# B2B_Connectors.net
KiCad netlist of a schematic drawn in Altium Designer
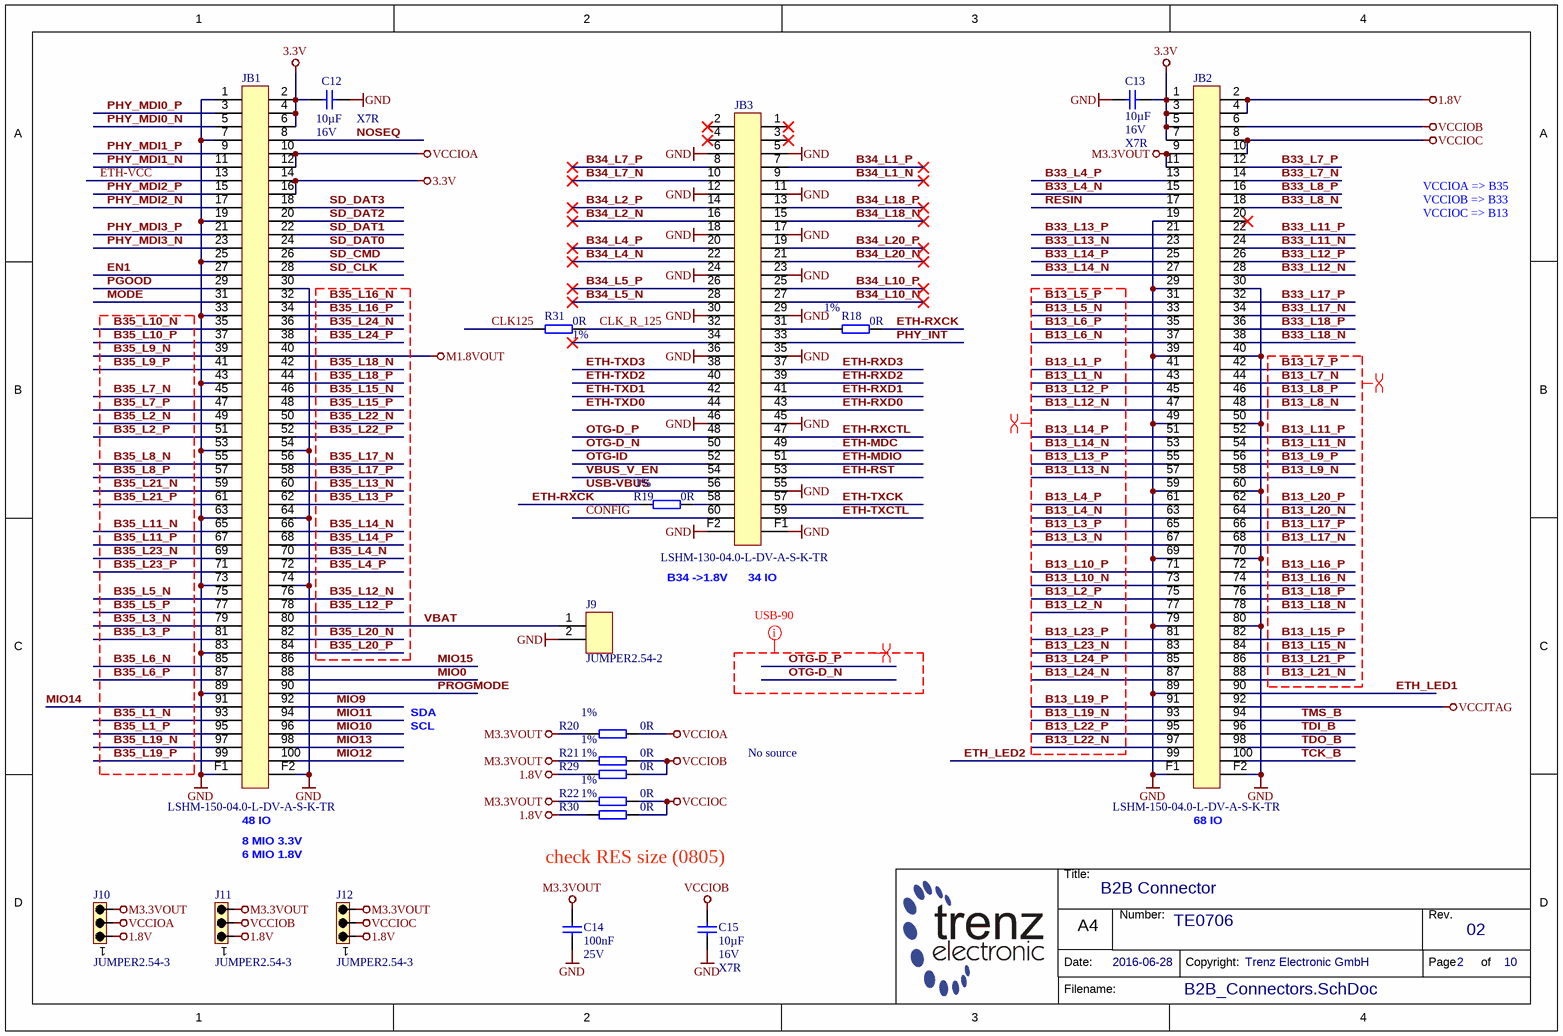
[diagram p0: B2B_Connectors.SchDoc]

(export (version "E")
  (design (tool "Eeschema 10.0.6"))
  (components
    (comp (ref "C12")
      (value "10µF")
      (footprint "CAPC2012X135N")
      (description "KON 10µF 16V X7R SMD 10%")
      (fields
        (field (name "VOLTAGE") "16V")
        (field (name "TECHNOLOGY") "X7R")
        (field (name "TOLERANCE") "10%")
      )
      (libsource (lib "TE") (part "CAP-NP"))
    )
    (comp (ref "C13")
      (value "10µF")
      (footprint "CAPC2012X135N")
      (description "KON 10µF 16V X7R SMD 10%")
      (fields
        (field (name "VOLTAGE") "16V")
        (field (name "TECHNOLOGY") "X7R")
        (field (name "TOLERANCE") "10%")
      )
      (libsource (lib "TE") (part "CAP-NP"))
    )
    (comp (ref "C14")
      (value "100nF")
      (footprint "CAPC1005X55N")
      (description "KON 100nF 25V X5R SMD")
      (fields (field (name "VOLTAGE") "25V"))
      (libsource (lib "TE") (part "CAP-NP"))
    )
    (comp (ref "C15")
      (value "10µF")
      (footprint "CAPC2012X135N")
      (description "KON 10µF 16V X7R SMD 10%")
      (fields
        (field (name "VOLTAGE") "16V")
        (field (name "TECHNOLOGY") "X7R")
        (field (name "TOLERANCE") "10%")
      )
      (libsource (lib "TE") (part "CAP-NP"))
    )
    (comp (ref "J9")
      (value "JUMPER2.54-2")
      (footprint "JUMPER2_54-2")
      (description "Stiftleiste gerade 1-reihig, 2pol.")
      (libsource (lib "TE") (part "CON-2"))
    )
    (comp (ref "J10")
      (value "JUMPER2.54-3")
      (footprint "JUMPER2_54-3")
      (description "Stiftleiste gerade 1-reihig, 3pol.")
      (libsource (lib "TE") (part "JUMPER2.54-3"))
    )
    (comp (ref "J11")
      (value "JUMPER2.54-3")
      (footprint "JUMPER2_54-3")
      (description "Stiftleiste gerade 1-reihig, 3pol.")
      (libsource (lib "TE") (part "JUMPER2.54-3"))
    )
    (comp (ref "J12")
      (value "JUMPER2.54-3")
      (footprint "JUMPER2_54-3")
      (description "Stiftleiste gerade 1-reihig, 3pol.")
      (libsource (lib "TE") (part "JUMPER2.54-3"))
    )
    (comp (ref "JB1")
      (value "LSHM-150-04.0-L-DV-A-S-K-TR")
      (footprint "LSHM-150-XXX-X-DV-A-X")
      (description "Samtec Razor Beam REF⁃189016⁃02, LF-04.0, 100 Pins, für alle 4x5 SoMs")
      (libsource (lib "TE") (part "LSHM-150-XXX-X-XX-A-X"))
    )
    (comp (ref "JB2")
      (value "LSHM-150-04.0-L-DV-A-S-K-TR")
      (footprint "LSHM-150-XXX-X-DV-A-X")
      (description "Samtec Razor Beam REF⁃189016⁃02, LF-04.0, 100 Pins, für alle 4x5 SoMs")
      (libsource (lib "TE") (part "LSHM-150-XXX-X-XX-A-X"))
    )
    (comp (ref "JB3")
      (value "LSHM-130-04.0-L-DV-A-S-K-TR")
      (footprint "LSHM-130-04.0-x-DV-A-S-K-TR")
      (description "Samtec Razor Beam REF⁃189017⁃02, LF-04.0, 60 Pins, für alle 4x5 SoMs")
      (libsource (lib "TE") (part "LSHM-130-XXX-X-XX-A-X"))
    )
    (comp (ref "R18")
      (value "0R")
      (footprint "RESC1005X40N")
      (description "WID SMD 0R")
      (fields (field (name "TOLERANCE") "1%"))
      (libsource (lib "TE") (part "RES"))
    )
    (comp (ref "R19")
      (value "0R")
      (footprint "RESC1005X40N")
      (description "WID SMD 0R")
      (fields (field (name "TOLERANCE") "1%"))
      (libsource (lib "TE") (part "RES"))
    )
    (comp (ref "R20")
      (value "0R")
      (footprint "RESC2012X60N")
      (description "WID SMD 0R 0.125W 2A Brücke")
      (fields (field (name "TOLERANCE") "1%"))
      (libsource (lib "TE") (part "RES"))
    )
    (comp (ref "R21")
      (value "0R")
      (footprint "RESC2012X60N")
      (description "WID SMD 0R 0.125W 2A Brücke")
      (fields (field (name "TOLERANCE") "1%"))
      (libsource (lib "TE") (part "RES"))
    )
    (comp (ref "R22")
      (value "0R")
      (footprint "RESC2012X60N")
      (description "WID SMD 0R 0.125W 2A Brücke")
      (fields (field (name "TOLERANCE") "1%"))
      (libsource (lib "TE") (part "RES"))
    )
    (comp (ref "R29")
      (value "0R")
      (footprint "RESC2012X60N")
      (description "WID SMD 0R 0.125W 2A Brücke")
      (fields (field (name "TOLERANCE") "1%"))
      (libsource (lib "TE") (part "RES"))
    )
    (comp (ref "R30")
      (value "0R")
      (footprint "RESC2012X60N")
      (description "WID SMD 0R 0.125W 2A Brücke")
      (fields (field (name "TOLERANCE") "1%"))
      (libsource (lib "TE") (part "RES"))
    )
    (comp (ref "R31")
      (value "0R")
      (footprint "RESC1005X40N")
      (description "WID SMD 0R")
      (fields (field (name "TOLERANCE") "1%"))
      (libsource (lib "TE") (part "RES"))
    )
  )
  (nets
    (net (code "1") (name "/B13_L1_N") (class "Default")
      (node (ref "JB2") (pin "43") (pinfunction "43_43") (pintype "passive"))
    )
    (net (code "2") (name "/B13_L1_P") (class "Default")
      (node (ref "JB2") (pin "41") (pinfunction "41_41") (pintype "passive"))
    )
    (net (code "3") (name "/B13_L2_N") (class "Default")
      (node (ref "JB2") (pin "77") (pinfunction "77_77") (pintype "passive"))
    )
    (net (code "4") (name "/B13_L2_P") (class "Default")
      (node (ref "JB2") (pin "75") (pinfunction "75_75") (pintype "passive"))
    )
    (net (code "5") (name "/B13_L3_N") (class "Default")
      (node (ref "JB2") (pin "67") (pinfunction "67_67") (pintype "passive"))
    )
    (net (code "6") (name "/B13_L3_P") (class "Default")
      (node (ref "JB2") (pin "65") (pinfunction "65_65") (pintype "passive"))
    )
    (net (code "7") (name "/B13_L4_N") (class "Default")
      (node (ref "JB2") (pin "63") (pinfunction "63_63") (pintype "passive"))
    )
    (net (code "8") (name "/B13_L4_P") (class "Default")
      (node (ref "JB2") (pin "61") (pinfunction "61_61") (pintype "passive"))
    )
    (net (code "9") (name "/B13_L5_N") (class "Default")
      (node (ref "JB2") (pin "33") (pinfunction "33_33") (pintype "passive"))
    )
    (net (code "10") (name "/B13_L5_P") (class "Default")
      (node (ref "JB2") (pin "31") (pinfunction "31_31") (pintype "passive"))
    )
    (net (code "11") (name "/B13_L6_N") (class "Default")
      (node (ref "JB2") (pin "37") (pinfunction "37_37") (pintype "passive"))
    )
    (net (code "12") (name "/B13_L6_P") (class "Default")
      (node (ref "JB2") (pin "35") (pinfunction "35_35") (pintype "passive"))
    )
    (net (code "13") (name "/B13_L7_N") (class "Default")
      (node (ref "JB2") (pin "44") (pinfunction "44_44") (pintype "passive"))
    )
    (net (code "14") (name "/B13_L7_P") (class "Default")
      (node (ref "JB2") (pin "42") (pinfunction "42_42") (pintype "passive"))
    )
    (net (code "15") (name "/B13_L8_N") (class "Default")
      (node (ref "JB2") (pin "48") (pinfunction "48_48") (pintype "passive"))
    )
    (net (code "16") (name "/B13_L8_P") (class "Default")
      (node (ref "JB2") (pin "46") (pinfunction "46_46") (pintype "passive"))
    )
    (net (code "17") (name "/B13_L9_N") (class "Default")
      (node (ref "JB2") (pin "58") (pinfunction "58_58") (pintype "passive"))
    )
    (net (code "18") (name "/B13_L9_P") (class "Default")
      (node (ref "JB2") (pin "56") (pinfunction "56_56") (pintype "passive"))
    )
    (net (code "19") (name "/B13_L10_N") (class "Default")
      (node (ref "JB2") (pin "73") (pinfunction "73_73") (pintype "passive"))
    )
    (net (code "20") (name "/B13_L10_P") (class "Default")
      (node (ref "JB2") (pin "71") (pinfunction "71_71") (pintype "passive"))
    )
    (net (code "21") (name "/B13_L11_N") (class "Default")
      (node (ref "JB2") (pin "54") (pinfunction "54_54") (pintype "passive"))
    )
    (net (code "22") (name "/B13_L11_P") (class "Default")
      (node (ref "JB2") (pin "52") (pinfunction "52_52") (pintype "passive"))
    )
    (net (code "23") (name "/B13_L12_N") (class "Default")
      (node (ref "JB2") (pin "47") (pinfunction "47_47") (pintype "passive"))
    )
    (net (code "24") (name "/B13_L12_P") (class "Default")
      (node (ref "JB2") (pin "45") (pinfunction "45_45") (pintype "passive"))
    )
    (net (code "25") (name "/B13_L13_N") (class "Default")
      (node (ref "JB2") (pin "57") (pinfunction "57_57") (pintype "passive"))
    )
    (net (code "26") (name "/B13_L13_P") (class "Default")
      (node (ref "JB2") (pin "55") (pinfunction "55_55") (pintype "passive"))
    )
    (net (code "27") (name "/B13_L14_N") (class "Default")
      (node (ref "JB2") (pin "53") (pinfunction "53_53") (pintype "passive"))
    )
    (net (code "28") (name "/B13_L14_P") (class "Default")
      (node (ref "JB2") (pin "51") (pinfunction "51_51") (pintype "passive"))
    )
    (net (code "29") (name "/B13_L15_N") (class "Default")
      (node (ref "JB2") (pin "84") (pinfunction "84_84") (pintype "passive"))
    )
    (net (code "30") (name "/B13_L15_P") (class "Default")
      (node (ref "JB2") (pin "82") (pinfunction "82_82") (pintype "passive"))
    )
    (net (code "31") (name "/B13_L16_N") (class "Default")
      (node (ref "JB2") (pin "74") (pinfunction "74_74") (pintype "passive"))
    )
    (net (code "32") (name "/B13_L16_P") (class "Default")
      (node (ref "JB2") (pin "72") (pinfunction "72_72") (pintype "passive"))
    )
    (net (code "33") (name "/B13_L17_N") (class "Default")
      (node (ref "JB2") (pin "68") (pinfunction "68_68") (pintype "passive"))
    )
    (net (code "34") (name "/B13_L17_P") (class "Default")
      (node (ref "JB2") (pin "66") (pinfunction "66_66") (pintype "passive"))
    )
    (net (code "35") (name "/B13_L18_N") (class "Default")
      (node (ref "JB2") (pin "78") (pinfunction "78_78") (pintype "passive"))
    )
    (net (code "36") (name "/B13_L18_P") (class "Default")
      (node (ref "JB2") (pin "76") (pinfunction "76_76") (pintype "passive"))
    )
    (net (code "37") (name "/B13_L19_N") (class "Default")
      (node (ref "JB2") (pin "93") (pinfunction "93_93") (pintype "passive"))
    )
    (net (code "38") (name "/B13_L19_P") (class "Default")
      (node (ref "JB2") (pin "91") (pinfunction "91_91") (pintype "passive"))
    )
    (net (code "39") (name "/B13_L20_N") (class "Default")
      (node (ref "JB2") (pin "64") (pinfunction "64_64") (pintype "passive"))
    )
    (net (code "40") (name "/B13_L20_P") (class "Default")
      (node (ref "JB2") (pin "62") (pinfunction "62_62") (pintype "passive"))
    )
    (net (code "41") (name "/B13_L21_N") (class "Default")
      (node (ref "JB2") (pin "88") (pinfunction "88_88") (pintype "passive"))
    )
    (net (code "42") (name "/B13_L21_P") (class "Default")
      (node (ref "JB2") (pin "86") (pinfunction "86_86") (pintype "passive"))
    )
    (net (code "43") (name "/B13_L22_N") (class "Default")
      (node (ref "JB2") (pin "97") (pinfunction "97_97") (pintype "passive"))
    )
    (net (code "44") (name "/B13_L22_P") (class "Default")
      (node (ref "JB2") (pin "95") (pinfunction "95_95") (pintype "passive"))
    )
    (net (code "45") (name "/B13_L23_N") (class "Default")
      (node (ref "JB2") (pin "83") (pinfunction "83_83") (pintype "passive"))
    )
    (net (code "46") (name "/B13_L23_P") (class "Default")
      (node (ref "JB2") (pin "81") (pinfunction "81_81") (pintype "passive"))
    )
    (net (code "47") (name "/B13_L24_N") (class "Default")
      (node (ref "JB2") (pin "87") (pinfunction "87_87") (pintype "passive"))
    )
    (net (code "48") (name "/B13_L24_P") (class "Default")
      (node (ref "JB2") (pin "85") (pinfunction "85_85") (pintype "passive"))
    )
    (net (code "49") (name "/B33_L4_N") (class "Default")
      (node (ref "JB2") (pin "15") (pinfunction "15_15") (pintype "passive"))
    )
    (net (code "50") (name "/B33_L4_P") (class "Default")
      (node (ref "JB2") (pin "13") (pinfunction "13_13") (pintype "passive"))
    )
    (net (code "51") (name "/B33_L7_N") (class "Default")
      (node (ref "JB2") (pin "14") (pinfunction "14_14") (pintype "passive"))
    )
    (net (code "52") (name "/B33_L7_P") (class "Default")
      (node (ref "JB2") (pin "12") (pinfunction "12_12") (pintype "passive"))
    )
    (net (code "53") (name "/B33_L8_N") (class "Default")
      (node (ref "JB2") (pin "18") (pinfunction "18_18") (pintype "passive"))
    )
    (net (code "54") (name "/B33_L8_P") (class "Default")
      (node (ref "JB2") (pin "16") (pinfunction "16_16") (pintype "passive"))
    )
    (net (code "55") (name "/B33_L11_N") (class "Default")
      (node (ref "JB2") (pin "24") (pinfunction "24_24") (pintype "passive"))
    )
    (net (code "56") (name "/B33_L11_P") (class "Default")
      (node (ref "JB2") (pin "22") (pinfunction "22_22") (pintype "passive"))
    )
    (net (code "57") (name "/B33_L12_N") (class "Default")
      (node (ref "JB2") (pin "28") (pinfunction "28_28") (pintype "passive"))
    )
    (net (code "58") (name "/B33_L12_P") (class "Default")
      (node (ref "JB2") (pin "26") (pinfunction "26_26") (pintype "passive"))
    )
    (net (code "59") (name "/B33_L13_N") (class "Default")
      (node (ref "JB2") (pin "23") (pinfunction "23_23") (pintype "passive"))
    )
    (net (code "60") (name "/B33_L13_P") (class "Default")
      (node (ref "JB2") (pin "21") (pinfunction "21_21") (pintype "passive"))
    )
    (net (code "61") (name "/B33_L14_N") (class "Default")
      (node (ref "JB2") (pin "27") (pinfunction "27_27") (pintype "passive"))
    )
    (net (code "62") (name "/B33_L14_P") (class "Default")
      (node (ref "JB2") (pin "25") (pinfunction "25_25") (pintype "passive"))
    )
    (net (code "63") (name "/B33_L17_N") (class "Default")
      (node (ref "JB2") (pin "34") (pinfunction "34_34") (pintype "passive"))
    )
    (net (code "64") (name "/B33_L17_P") (class "Default")
      (node (ref "JB2") (pin "32") (pinfunction "32_32") (pintype "passive"))
    )
    (net (code "65") (name "/B33_L18_N") (class "Default")
      (node (ref "JB2") (pin "38") (pinfunction "38_38") (pintype "passive"))
    )
    (net (code "66") (name "/B33_L18_P") (class "Default")
      (node (ref "JB2") (pin "36") (pinfunction "36_36") (pintype "passive"))
    )
    (net (code "67") (name "/B34_L1_N") (class "Default")
      (node (ref "JB3") (pin "9") (pinfunction "9_9") (pintype "passive+no_connect"))
    )
    (net (code "68") (name "/B34_L1_P") (class "Default")
      (node (ref "JB3") (pin "7") (pinfunction "7_7") (pintype "passive+no_connect"))
    )
    (net (code "69") (name "/B34_L2_N") (class "Default")
      (node (ref "JB3") (pin "16") (pinfunction "16_16") (pintype "passive+no_connect"))
    )
    (net (code "70") (name "/B34_L2_P") (class "Default")
      (node (ref "JB3") (pin "14") (pinfunction "14_14") (pintype "passive+no_connect"))
    )
    (net (code "71") (name "/B34_L4_N") (class "Default")
      (node (ref "JB3") (pin "22") (pinfunction "22_22") (pintype "passive+no_connect"))
    )
    (net (code "72") (name "/B34_L4_P") (class "Default")
      (node (ref "JB3") (pin "20") (pinfunction "20_20") (pintype "passive+no_connect"))
    )
    (net (code "73") (name "/B34_L5_N") (class "Default")
      (node (ref "JB3") (pin "28") (pinfunction "28_28") (pintype "passive+no_connect"))
    )
    (net (code "74") (name "/B34_L5_P") (class "Default")
      (node (ref "JB3") (pin "26") (pinfunction "26_26") (pintype "passive+no_connect"))
    )
    (net (code "75") (name "/B34_L7_N") (class "Default")
      (node (ref "JB3") (pin "10") (pinfunction "10_10") (pintype "passive+no_connect"))
    )
    (net (code "76") (name "/B34_L7_P") (class "Default")
      (node (ref "JB3") (pin "8") (pinfunction "8_8") (pintype "passive+no_connect"))
    )
    (net (code "77") (name "/B34_L10_N") (class "Default")
      (node (ref "JB3") (pin "27") (pinfunction "27_27") (pintype "passive+no_connect"))
    )
    (net (code "78") (name "/B34_L10_P") (class "Default")
      (node (ref "JB3") (pin "25") (pinfunction "25_25") (pintype "passive+no_connect"))
    )
    (net (code "79") (name "/B34_L18_N") (class "Default")
      (node (ref "JB3") (pin "15") (pinfunction "15_15") (pintype "passive+no_connect"))
    )
    (net (code "80") (name "/B34_L18_P") (class "Default")
      (node (ref "JB3") (pin "13") (pinfunction "13_13") (pintype "passive+no_connect"))
    )
    (net (code "81") (name "/B34_L20_N") (class "Default")
      (node (ref "JB3") (pin "21") (pinfunction "21_21") (pintype "passive+no_connect"))
    )
    (net (code "82") (name "/B34_L20_P") (class "Default")
      (node (ref "JB3") (pin "19") (pinfunction "19_19") (pintype "passive+no_connect"))
    )
    (net (code "83") (name "/B35_L1_N") (class "Default")
      (node (ref "JB1") (pin "93") (pinfunction "93_93") (pintype "passive"))
    )
    (net (code "84") (name "/B35_L1_P") (class "Default")
      (node (ref "JB1") (pin "95") (pinfunction "95_95") (pintype "passive"))
    )
    (net (code "85") (name "/B35_L2_N") (class "Default")
      (node (ref "JB1") (pin "49") (pinfunction "49_49") (pintype "passive"))
    )
    (net (code "86") (name "/B35_L2_P") (class "Default")
      (node (ref "JB1") (pin "51") (pinfunction "51_51") (pintype "passive"))
    )
    (net (code "87") (name "/B35_L3_N") (class "Default")
      (node (ref "JB1") (pin "79") (pinfunction "79_79") (pintype "passive"))
    )
    (net (code "88") (name "/B35_L3_P") (class "Default")
      (node (ref "JB1") (pin "81") (pinfunction "81_81") (pintype "passive"))
    )
    (net (code "89") (name "/B35_L4_N") (class "Default")
      (node (ref "JB1") (pin "70") (pinfunction "70_70") (pintype "passive"))
    )
    (net (code "90") (name "/B35_L4_P") (class "Default")
      (node (ref "JB1") (pin "72") (pinfunction "72_72") (pintype "passive"))
    )
    (net (code "91") (name "/B35_L5_N") (class "Default")
      (node (ref "JB1") (pin "75") (pinfunction "75_75") (pintype "passive"))
    )
    (net (code "92") (name "/B35_L5_P") (class "Default")
      (node (ref "JB1") (pin "77") (pinfunction "77_77") (pintype "passive"))
    )
    (net (code "93") (name "/B35_L6_N") (class "Default")
      (node (ref "JB1") (pin "85") (pinfunction "85_85") (pintype "passive"))
    )
    (net (code "94") (name "/B35_L6_P") (class "Default")
      (node (ref "JB1") (pin "87") (pinfunction "87_87") (pintype "passive"))
    )
    (net (code "95") (name "/B35_L7_N") (class "Default")
      (node (ref "JB1") (pin "45") (pinfunction "45_45") (pintype "passive"))
    )
    (net (code "96") (name "/B35_L7_P") (class "Default")
      (node (ref "JB1") (pin "47") (pinfunction "47_47") (pintype "passive"))
    )
    (net (code "97") (name "/B35_L8_N") (class "Default")
      (node (ref "JB1") (pin "55") (pinfunction "55_55") (pintype "passive"))
    )
    (net (code "98") (name "/B35_L8_P") (class "Default")
      (node (ref "JB1") (pin "57") (pinfunction "57_57") (pintype "passive"))
    )
    (net (code "99") (name "/B35_L9_N") (class "Default")
      (node (ref "JB1") (pin "39") (pinfunction "39_39") (pintype "passive"))
    )
    (net (code "100") (name "/B35_L9_P") (class "Default")
      (node (ref "JB1") (pin "41") (pinfunction "41_41") (pintype "passive"))
    )
    (net (code "101") (name "/B35_L10_N") (class "Default")
      (node (ref "JB1") (pin "35") (pinfunction "35_35") (pintype "passive"))
    )
    (net (code "102") (name "/B35_L10_P") (class "Default")
      (node (ref "JB1") (pin "37") (pinfunction "37_37") (pintype "passive"))
    )
    (net (code "103") (name "/B35_L11_N") (class "Default")
      (node (ref "JB1") (pin "65") (pinfunction "65_65") (pintype "passive"))
    )
    (net (code "104") (name "/B35_L11_P") (class "Default")
      (node (ref "JB1") (pin "67") (pinfunction "67_67") (pintype "passive"))
    )
    (net (code "105") (name "/B35_L12_N") (class "Default")
      (node (ref "JB1") (pin "76") (pinfunction "76_76") (pintype "passive"))
    )
    (net (code "106") (name "/B35_L12_P") (class "Default")
      (node (ref "JB1") (pin "78") (pinfunction "78_78") (pintype "passive"))
    )
    (net (code "107") (name "/B35_L13_N") (class "Default")
      (node (ref "JB1") (pin "60") (pinfunction "60_60") (pintype "passive"))
    )
    (net (code "108") (name "/B35_L13_P") (class "Default")
      (node (ref "JB1") (pin "62") (pinfunction "62_62") (pintype "passive"))
    )
    (net (code "109") (name "/B35_L14_N") (class "Default")
      (node (ref "JB1") (pin "66") (pinfunction "66_66") (pintype "passive"))
    )
    (net (code "110") (name "/B35_L14_P") (class "Default")
      (node (ref "JB1") (pin "68") (pinfunction "68_68") (pintype "passive"))
    )
    (net (code "111") (name "/B35_L15_N") (class "Default")
      (node (ref "JB1") (pin "46") (pinfunction "46_46") (pintype "passive"))
    )
    (net (code "112") (name "/B35_L15_P") (class "Default")
      (node (ref "JB1") (pin "48") (pinfunction "48_48") (pintype "passive"))
    )
    (net (code "113") (name "/B35_L16_N") (class "Default")
      (node (ref "JB1") (pin "32") (pinfunction "32_32") (pintype "passive"))
    )
    (net (code "114") (name "/B35_L16_P") (class "Default")
      (node (ref "JB1") (pin "34") (pinfunction "34_34") (pintype "passive"))
    )
    (net (code "115") (name "/B35_L17_N") (class "Default")
      (node (ref "JB1") (pin "56") (pinfunction "56_56") (pintype "passive"))
    )
    (net (code "116") (name "/B35_L17_P") (class "Default")
      (node (ref "JB1") (pin "58") (pinfunction "58_58") (pintype "passive"))
    )
    (net (code "117") (name "/B35_L18_N") (class "Default")
      (node (ref "JB1") (pin "42") (pinfunction "42_42") (pintype "passive"))
    )
    (net (code "118") (name "/B35_L18_P") (class "Default")
      (node (ref "JB1") (pin "44") (pinfunction "44_44") (pintype "passive"))
    )
    (net (code "119") (name "/B35_L19_N") (class "Default")
      (node (ref "JB1") (pin "97") (pinfunction "97_97") (pintype "passive"))
    )
    (net (code "120") (name "/B35_L19_P") (class "Default")
      (node (ref "JB1") (pin "99") (pinfunction "99_99") (pintype "passive"))
    )
    (net (code "121") (name "/B35_L20_N") (class "Default")
      (node (ref "JB1") (pin "82") (pinfunction "82_82") (pintype "passive"))
    )
    (net (code "122") (name "/B35_L20_P") (class "Default")
      (node (ref "JB1") (pin "84") (pinfunction "84_84") (pintype "passive"))
    )
    (net (code "123") (name "/B35_L21_N") (class "Default")
      (node (ref "JB1") (pin "59") (pinfunction "59_59") (pintype "passive"))
    )
    (net (code "124") (name "/B35_L21_P") (class "Default")
      (node (ref "JB1") (pin "61") (pinfunction "61_61") (pintype "passive"))
    )
    (net (code "125") (name "/B35_L22_N") (class "Default")
      (node (ref "JB1") (pin "50") (pinfunction "50_50") (pintype "passive"))
    )
    (net (code "126") (name "/B35_L22_P") (class "Default")
      (node (ref "JB1") (pin "52") (pinfunction "52_52") (pintype "passive"))
    )
    (net (code "127") (name "/B35_L23_N") (class "Default")
      (node (ref "JB1") (pin "69") (pinfunction "69_69") (pintype "passive"))
    )
    (net (code "128") (name "/B35_L23_P") (class "Default")
      (node (ref "JB1") (pin "71") (pinfunction "71_71") (pintype "passive"))
    )
    (net (code "129") (name "/B35_L24_N") (class "Default")
      (node (ref "JB1") (pin "36") (pinfunction "36_36") (pintype "passive"))
    )
    (net (code "130") (name "/B35_L24_P") (class "Default")
      (node (ref "JB1") (pin "38") (pinfunction "38_38") (pintype "passive"))
    )
    (net (code "131") (name "/CLK125") (class "Default")
      (node (ref "R31") (pin "1") (pinfunction "1_1") (pintype "passive"))
    )
    (net (code "132") (name "/CLK_R_125") (class "Default")
      (node (ref "JB3") (pin "32") (pinfunction "32_32") (pintype "passive"))
      (node (ref "R31") (pin "2") (pinfunction "2_2") (pintype "passive"))
    )
    (net (code "133") (name "/CONFIG") (class "Default")
      (node (ref "JB3") (pin "60") (pinfunction "60_60") (pintype "passive"))
    )
    (net (code "134") (name "/EN1") (class "Default")
      (node (ref "JB1") (pin "27") (pinfunction "27_27") (pintype "passive"))
    )
    (net (code "135") (name "/ETH-MDC") (class "Default")
      (node (ref "JB3") (pin "49") (pinfunction "49_49") (pintype "passive"))
    )
    (net (code "136") (name "/ETH-MDIO") (class "Default")
      (node (ref "JB3") (pin "51") (pinfunction "51_51") (pintype "passive"))
    )
    (net (code "137") (name "/ETH-RST") (class "Default")
      (node (ref "JB3") (pin "53") (pinfunction "53_53") (pintype "passive"))
    )
    (net (code "138") (name "/ETH-RXCK") (class "Default")
      (node (ref "R18") (pin "2") (pinfunction "2_2") (pintype "passive"))
      (node (ref "R19") (pin "1") (pinfunction "1_1") (pintype "passive"))
    )
    (net (code "139") (name "/ETH-RXCTL") (class "Default")
      (node (ref "JB3") (pin "47") (pinfunction "47_47") (pintype "passive"))
    )
    (net (code "140") (name "/ETH-RXD0") (class "Default")
      (node (ref "JB3") (pin "43") (pinfunction "43_43") (pintype "passive"))
    )
    (net (code "141") (name "/ETH-RXD1") (class "Default")
      (node (ref "JB3") (pin "41") (pinfunction "41_41") (pintype "passive"))
    )
    (net (code "142") (name "/ETH-RXD2") (class "Default")
      (node (ref "JB3") (pin "39") (pinfunction "39_39") (pintype "passive"))
    )
    (net (code "143") (name "/ETH-RXD3") (class "Default")
      (node (ref "JB3") (pin "37") (pinfunction "37_37") (pintype "passive"))
    )
    (net (code "144") (name "/ETH-TXCK") (class "Default")
      (node (ref "JB3") (pin "57") (pinfunction "57_57") (pintype "passive"))
    )
    (net (code "145") (name "/ETH-TXCTL") (class "Default")
      (node (ref "JB3") (pin "59") (pinfunction "59_59") (pintype "passive"))
    )
    (net (code "146") (name "/ETH-TXD0") (class "Default")
      (node (ref "JB3") (pin "44") (pinfunction "44_44") (pintype "passive"))
    )
    (net (code "147") (name "/ETH-TXD1") (class "Default")
      (node (ref "JB3") (pin "42") (pinfunction "42_42") (pintype "passive"))
    )
    (net (code "148") (name "/ETH-TXD2") (class "Default")
      (node (ref "JB3") (pin "40") (pinfunction "40_40") (pintype "passive"))
    )
    (net (code "149") (name "/ETH-TXD3") (class "Default")
      (node (ref "JB3") (pin "38") (pinfunction "38_38") (pintype "passive"))
    )
    (net (code "150") (name "/ETH-VCC") (class "Default")
      (node (ref "JB1") (pin "13") (pinfunction "13_13") (pintype "passive"))
    )
    (net (code "151") (name "/ETH_LED1") (class "Default")
      (node (ref "JB2") (pin "90") (pinfunction "90_90") (pintype "passive"))
    )
    (net (code "152") (name "/ETH_LED2") (class "Default")
      (node (ref "JB2") (pin "99") (pinfunction "99_99") (pintype "passive"))
    )
    (net (code "153") (name "/MIO0") (class "Default")
      (node (ref "JB1") (pin "88") (pinfunction "88_88") (pintype "passive"))
    )
    (net (code "154") (name "/MIO9") (class "Default")
      (node (ref "JB1") (pin "92") (pinfunction "92_92") (pintype "passive"))
    )
    (net (code "155") (name "/MIO10") (class "Default")
      (node (ref "JB1") (pin "96") (pinfunction "96_96") (pintype "passive"))
    )
    (net (code "156") (name "/MIO11") (class "Default")
      (node (ref "JB1") (pin "94") (pinfunction "94_94") (pintype "passive"))
    )
    (net (code "157") (name "/MIO12") (class "Default")
      (node (ref "JB1") (pin "100") (pinfunction "100_100") (pintype "passive"))
    )
    (net (code "158") (name "/MIO13") (class "Default")
      (node (ref "JB1") (pin "98") (pinfunction "98_98") (pintype "passive"))
    )
    (net (code "159") (name "/MIO14") (class "Default")
      (node (ref "JB1") (pin "91") (pinfunction "91_91") (pintype "passive"))
    )
    (net (code "160") (name "/MIO15") (class "Default")
      (node (ref "JB1") (pin "86") (pinfunction "86_86") (pintype "passive"))
    )
    (net (code "161") (name "/MODE") (class "Default")
      (node (ref "JB1") (pin "31") (pinfunction "31_31") (pintype "passive"))
    )
    (net (code "162") (name "/NOSEQ") (class "Default")
      (node (ref "JB1") (pin "8") (pinfunction "8_8") (pintype "passive"))
    )
    (net (code "163") (name "/OTG-D_N") (class "Default")
      (node (ref "JB3") (pin "50") (pinfunction "50_50") (pintype "passive"))
    )
    (net (code "164") (name "/OTG-D_P") (class "Default")
      (node (ref "JB3") (pin "48") (pinfunction "48_48") (pintype "passive"))
    )
    (net (code "165") (name "/OTG-ID") (class "Default")
      (node (ref "JB3") (pin "52") (pinfunction "52_52") (pintype "passive"))
    )
    (net (code "166") (name "/PGOOD") (class "Default")
      (node (ref "JB1") (pin "29") (pinfunction "29_29") (pintype "passive"))
    )
    (net (code "167") (name "/PHY_INT") (class "Default")
      (node (ref "JB3") (pin "33") (pinfunction "33_33") (pintype "passive"))
    )
    (net (code "168") (name "/PHY_MDI0_N") (class "Default")
      (node (ref "JB1") (pin "5") (pinfunction "5_5") (pintype "passive"))
    )
    (net (code "169") (name "/PHY_MDI0_P") (class "Default")
      (node (ref "JB1") (pin "3") (pinfunction "3_3") (pintype "passive"))
    )
    (net (code "170") (name "/PHY_MDI1_N") (class "Default")
      (node (ref "JB1") (pin "11") (pinfunction "11_11") (pintype "passive"))
    )
    (net (code "171") (name "/PHY_MDI1_P") (class "Default")
      (node (ref "JB1") (pin "9") (pinfunction "9_9") (pintype "passive"))
    )
    (net (code "172") (name "/PHY_MDI2_N") (class "Default")
      (node (ref "JB1") (pin "17") (pinfunction "17_17") (pintype "passive"))
    )
    (net (code "173") (name "/PHY_MDI2_P") (class "Default")
      (node (ref "JB1") (pin "15") (pinfunction "15_15") (pintype "passive"))
    )
    (net (code "174") (name "/PHY_MDI3_N") (class "Default")
      (node (ref "JB1") (pin "23") (pinfunction "23_23") (pintype "passive"))
    )
    (net (code "175") (name "/PHY_MDI3_P") (class "Default")
      (node (ref "JB1") (pin "21") (pinfunction "21_21") (pintype "passive"))
    )
    (net (code "176") (name "/PROGMODE") (class "Default")
      (node (ref "JB1") (pin "90") (pinfunction "90_90") (pintype "passive"))
    )
    (net (code "177") (name "/RESIN") (class "Default")
      (node (ref "JB2") (pin "17") (pinfunction "17_17") (pintype "passive"))
    )
    (net (code "178") (name "/SD_CLK") (class "Default")
      (node (ref "JB1") (pin "28") (pinfunction "28_28") (pintype "passive"))
    )
    (net (code "179") (name "/SD_CMD") (class "Default")
      (node (ref "JB1") (pin "26") (pinfunction "26_26") (pintype "passive"))
    )
    (net (code "180") (name "/SD_DAT0") (class "Default")
      (node (ref "JB1") (pin "24") (pinfunction "24_24") (pintype "passive"))
    )
    (net (code "181") (name "/SD_DAT1") (class "Default")
      (node (ref "JB1") (pin "22") (pinfunction "22_22") (pintype "passive"))
    )
    (net (code "182") (name "/SD_DAT2") (class "Default")
      (node (ref "JB1") (pin "20") (pinfunction "20_20") (pintype "passive"))
    )
    (net (code "183") (name "/SD_DAT3") (class "Default")
      (node (ref "JB1") (pin "18") (pinfunction "18_18") (pintype "passive"))
    )
    (net (code "184") (name "/TCK_B") (class "Default")
      (node (ref "JB2") (pin "100") (pinfunction "100_100") (pintype "passive"))
    )
    (net (code "185") (name "/TDI_B") (class "Default")
      (node (ref "JB2") (pin "96") (pinfunction "96_96") (pintype "passive"))
    )
    (net (code "186") (name "/TDO_B") (class "Default")
      (node (ref "JB2") (pin "98") (pinfunction "98_98") (pintype "passive"))
    )
    (net (code "187") (name "/TMS_B") (class "Default")
      (node (ref "JB2") (pin "94") (pinfunction "94_94") (pintype "passive"))
    )
    (net (code "188") (name "/USB-VBUS") (class "Default")
      (node (ref "JB3") (pin "56") (pinfunction "56_56") (pintype "passive"))
    )
    (net (code "189") (name "/VBAT") (class "Default")
      (node (ref "J9") (pin "1") (pinfunction "1_1") (pintype "passive"))
      (node (ref "JB1") (pin "80") (pinfunction "80_80") (pintype "passive"))
    )
    (net (code "190") (name "/VBUS_V_EN") (class "Default")
      (node (ref "JB3") (pin "54") (pinfunction "54_54") (pintype "passive"))
    )
    (net (code "191") (name "1.8V") (class "Default")
      (node (ref "J10") (pin "1") (pinfunction "1_1") (pintype "passive"))
      (node (ref "J11") (pin "1") (pinfunction "1_1") (pintype "passive"))
      (node (ref "J12") (pin "1") (pinfunction "1_1") (pintype "passive"))
      (node (ref "JB2") (pin "2") (pinfunction "2_2") (pintype "passive"))
      (node (ref "JB2") (pin "4") (pinfunction "4_4") (pintype "passive"))
      (node (ref "R29") (pin "1") (pinfunction "1_1") (pintype "passive"))
      (node (ref "R30") (pin "1") (pinfunction "1_1") (pintype "passive"))
    )
    (net (code "192") (name "3.3V") (class "Default")
      (node (ref "C12") (pin "2") (pinfunction "2_2") (pintype "passive"))
      (node (ref "C13") (pin "2") (pinfunction "2_2") (pintype "passive"))
      (node (ref "JB1") (pin "14") (pinfunction "14_14") (pintype "passive"))
      (node (ref "JB1") (pin "16") (pinfunction "16_16") (pintype "passive"))
      (node (ref "JB1") (pin "2") (pinfunction "2_2") (pintype "passive"))
      (node (ref "JB1") (pin "4") (pinfunction "4_4") (pintype "passive"))
      (node (ref "JB1") (pin "6") (pinfunction "6_6") (pintype "passive"))
      (node (ref "JB2") (pin "1") (pinfunction "1_1") (pintype "passive"))
      (node (ref "JB2") (pin "3") (pinfunction "3_3") (pintype "passive"))
      (node (ref "JB2") (pin "5") (pinfunction "5_5") (pintype "passive"))
      (node (ref "JB2") (pin "7") (pinfunction "7_7") (pintype "passive"))
    )
    (net (code "193") (name "GND") (class "Default")
      (node (ref "C12") (pin "1") (pinfunction "1_1") (pintype "passive"))
      (node (ref "C13") (pin "1") (pinfunction "1_1") (pintype "passive"))
      (node (ref "C14") (pin "2") (pinfunction "2_2") (pintype "passive"))
      (node (ref "C15") (pin "1") (pinfunction "1_1") (pintype "passive"))
      (node (ref "J9") (pin "2") (pinfunction "2_2") (pintype "passive"))
      (node (ref "JB1") (pin "1") (pinfunction "1_1") (pintype "passive"))
      (node (ref "JB1") (pin "19") (pinfunction "19_19") (pintype "passive"))
      (node (ref "JB1") (pin "25") (pinfunction "25_25") (pintype "passive"))
      (node (ref "JB1") (pin "30") (pinfunction "30_30") (pintype "passive"))
      (node (ref "JB1") (pin "33") (pinfunction "33_33") (pintype "passive"))
      (node (ref "JB1") (pin "43") (pinfunction "43_43") (pintype "passive"))
      (node (ref "JB1") (pin "53") (pinfunction "53_53") (pintype "passive"))
      (node (ref "JB1") (pin "54") (pinfunction "54_54") (pintype "passive"))
      (node (ref "JB1") (pin "63") (pinfunction "63_63") (pintype "passive"))
      (node (ref "JB1") (pin "64") (pinfunction "64_64") (pintype "passive"))
      (node (ref "JB1") (pin "7") (pinfunction "7_7") (pintype "passive"))
      (node (ref "JB1") (pin "73") (pinfunction "73_73") (pintype "passive"))
      (node (ref "JB1") (pin "74") (pinfunction "74_74") (pintype "passive"))
      (node (ref "JB1") (pin "83") (pinfunction "83_83") (pintype "passive"))
      (node (ref "JB1") (pin "89") (pinfunction "89_89") (pintype "passive"))
      (node (ref "JB1") (pin "F1") (pinfunction "Shield_F1") (pintype "passive"))
      (node (ref "JB1") (pin "F2") (pinfunction "Shield_F2") (pintype "passive"))
      (node (ref "JB2") (pin "19") (pinfunction "19_19") (pintype "passive"))
      (node (ref "JB2") (pin "29") (pinfunction "29_29") (pintype "passive"))
      (node (ref "JB2") (pin "30") (pinfunction "30_30") (pintype "passive"))
      (node (ref "JB2") (pin "39") (pinfunction "39_39") (pintype "passive"))
      (node (ref "JB2") (pin "40") (pinfunction "40_40") (pintype "passive"))
      (node (ref "JB2") (pin "49") (pinfunction "49_49") (pintype "passive"))
      (node (ref "JB2") (pin "50") (pinfunction "50_50") (pintype "passive"))
      (node (ref "JB2") (pin "59") (pinfunction "59_59") (pintype "passive"))
      (node (ref "JB2") (pin "60") (pinfunction "60_60") (pintype "passive"))
      (node (ref "JB2") (pin "69") (pinfunction "69_69") (pintype "passive"))
      (node (ref "JB2") (pin "70") (pinfunction "70_70") (pintype "passive"))
      (node (ref "JB2") (pin "79") (pinfunction "79_79") (pintype "passive"))
      (node (ref "JB2") (pin "80") (pinfunction "80_80") (pintype "passive"))
      (node (ref "JB2") (pin "89") (pinfunction "89_89") (pintype "passive"))
      (node (ref "JB2") (pin "F1") (pinfunction "Shield_F1") (pintype "passive"))
      (node (ref "JB2") (pin "F2") (pinfunction "Shield_F2") (pintype "passive"))
      (node (ref "JB3") (pin "11") (pinfunction "11_11") (pintype "passive"))
      (node (ref "JB3") (pin "12") (pinfunction "12_12") (pintype "passive"))
      (node (ref "JB3") (pin "17") (pinfunction "17_17") (pintype "passive"))
      (node (ref "JB3") (pin "18") (pinfunction "18_18") (pintype "passive"))
      (node (ref "JB3") (pin "23") (pinfunction "23_23") (pintype "passive"))
      (node (ref "JB3") (pin "24") (pinfunction "24_24") (pintype "passive"))
      (node (ref "JB3") (pin "29") (pinfunction "29_29") (pintype "passive"))
      (node (ref "JB3") (pin "30") (pinfunction "30_30") (pintype "passive"))
      (node (ref "JB3") (pin "35") (pinfunction "35_35") (pintype "passive"))
      (node (ref "JB3") (pin "36") (pinfunction "36_36") (pintype "passive"))
      (node (ref "JB3") (pin "45") (pinfunction "45_45") (pintype "passive"))
      (node (ref "JB3") (pin "46") (pinfunction "46_46") (pintype "passive"))
      (node (ref "JB3") (pin "5") (pinfunction "5_5") (pintype "passive"))
      (node (ref "JB3") (pin "55") (pinfunction "55_55") (pintype "passive"))
      (node (ref "JB3") (pin "6") (pinfunction "6_6") (pintype "passive"))
      (node (ref "JB3") (pin "F1") (pinfunction "Shield_F1") (pintype "passive"))
      (node (ref "JB3") (pin "F2") (pinfunction "Shield_F2") (pintype "passive"))
    )
    (net (code "194") (name "M1.8VOUT") (class "Default")
      (node (ref "JB1") (pin "40") (pinfunction "40_40") (pintype "passive"))
    )
    (net (code "195") (name "M3.3VOUT") (class "Default")
      (node (ref "C14") (pin "1") (pinfunction "1_1") (pintype "passive"))
      (node (ref "J10") (pin "3") (pinfunction "3_3") (pintype "passive"))
      (node (ref "J11") (pin "3") (pinfunction "3_3") (pintype "passive"))
      (node (ref "J12") (pin "3") (pinfunction "3_3") (pintype "passive"))
      (node (ref "JB2") (pin "11") (pinfunction "11_11") (pintype "passive"))
      (node (ref "JB2") (pin "9") (pinfunction "9_9") (pintype "passive"))
      (node (ref "R20") (pin "1") (pinfunction "1_1") (pintype "passive"))
      (node (ref "R21") (pin "1") (pinfunction "1_1") (pintype "passive"))
      (node (ref "R22") (pin "1") (pinfunction "1_1") (pintype "passive"))
    )
    (net (code "196") (name "Net-(JB3-Pad31)") (class "Default")
      (node (ref "JB3") (pin "31") (pinfunction "31_31") (pintype "passive"))
      (node (ref "R18") (pin "1") (pinfunction "1_1") (pintype "passive"))
    )
    (net (code "197") (name "Net-(JB3-Pad58)") (class "Default")
      (node (ref "JB3") (pin "58") (pinfunction "58_58") (pintype "passive"))
      (node (ref "R19") (pin "2") (pinfunction "2_2") (pintype "passive"))
    )
    (net (code "198") (name "VCCIOA") (class "Default")
      (node (ref "J10") (pin "2") (pinfunction "2_2") (pintype "passive"))
      (node (ref "JB1") (pin "10") (pinfunction "10_10") (pintype "passive"))
      (node (ref "JB1") (pin "12") (pinfunction "12_12") (pintype "passive"))
      (node (ref "R20") (pin "2") (pinfunction "2_2") (pintype "passive"))
    )
    (net (code "199") (name "VCCIOB") (class "Default")
      (node (ref "C15") (pin "2") (pinfunction "2_2") (pintype "passive"))
      (node (ref "J11") (pin "2") (pinfunction "2_2") (pintype "passive"))
      (node (ref "JB2") (pin "6") (pinfunction "6_6") (pintype "passive"))
      (node (ref "R21") (pin "2") (pinfunction "2_2") (pintype "passive"))
      (node (ref "R29") (pin "2") (pinfunction "2_2") (pintype "passive"))
    )
    (net (code "200") (name "VCCIOC") (class "Default")
      (node (ref "J12") (pin "2") (pinfunction "2_2") (pintype "passive"))
      (node (ref "JB2") (pin "10") (pinfunction "10_10") (pintype "passive"))
      (node (ref "JB2") (pin "8") (pinfunction "8_8") (pintype "passive"))
      (node (ref "R22") (pin "2") (pinfunction "2_2") (pintype "passive"))
      (node (ref "R30") (pin "2") (pinfunction "2_2") (pintype "passive"))
    )
    (net (code "201") (name "VCCJTAG") (class "Default")
      (node (ref "JB2") (pin "92") (pinfunction "92_92") (pintype "passive"))
    )
    (net (code "202") (name "unconnected-(JB2-Pad20)") (class "Default")
      (node (ref "JB2") (pin "20") (pinfunction "20_20") (pintype "passive+no_connect"))
    )
    (net (code "203") (name "unconnected-(JB3-Pad1)") (class "Default")
      (node (ref "JB3") (pin "1") (pinfunction "1_1") (pintype "passive+no_connect"))
    )
    (net (code "204") (name "unconnected-(JB3-Pad2)") (class "Default")
      (node (ref "JB3") (pin "2") (pinfunction "2_2") (pintype "passive+no_connect"))
    )
    (net (code "205") (name "unconnected-(JB3-Pad3)") (class "Default")
      (node (ref "JB3") (pin "3") (pinfunction "3_3") (pintype "passive+no_connect"))
    )
    (net (code "206") (name "unconnected-(JB3-Pad4)") (class "Default")
      (node (ref "JB3") (pin "4") (pinfunction "4_4") (pintype "passive+no_connect"))
    )
    (net (code "207") (name "unconnected-(JB3-Pad34)") (class "Default")
      (node (ref "JB3") (pin "34") (pinfunction "34_34") (pintype "passive+no_connect"))
    )
  )
)
